# hub4.net
KiCad netlist of a schematic drawn in EAGLE
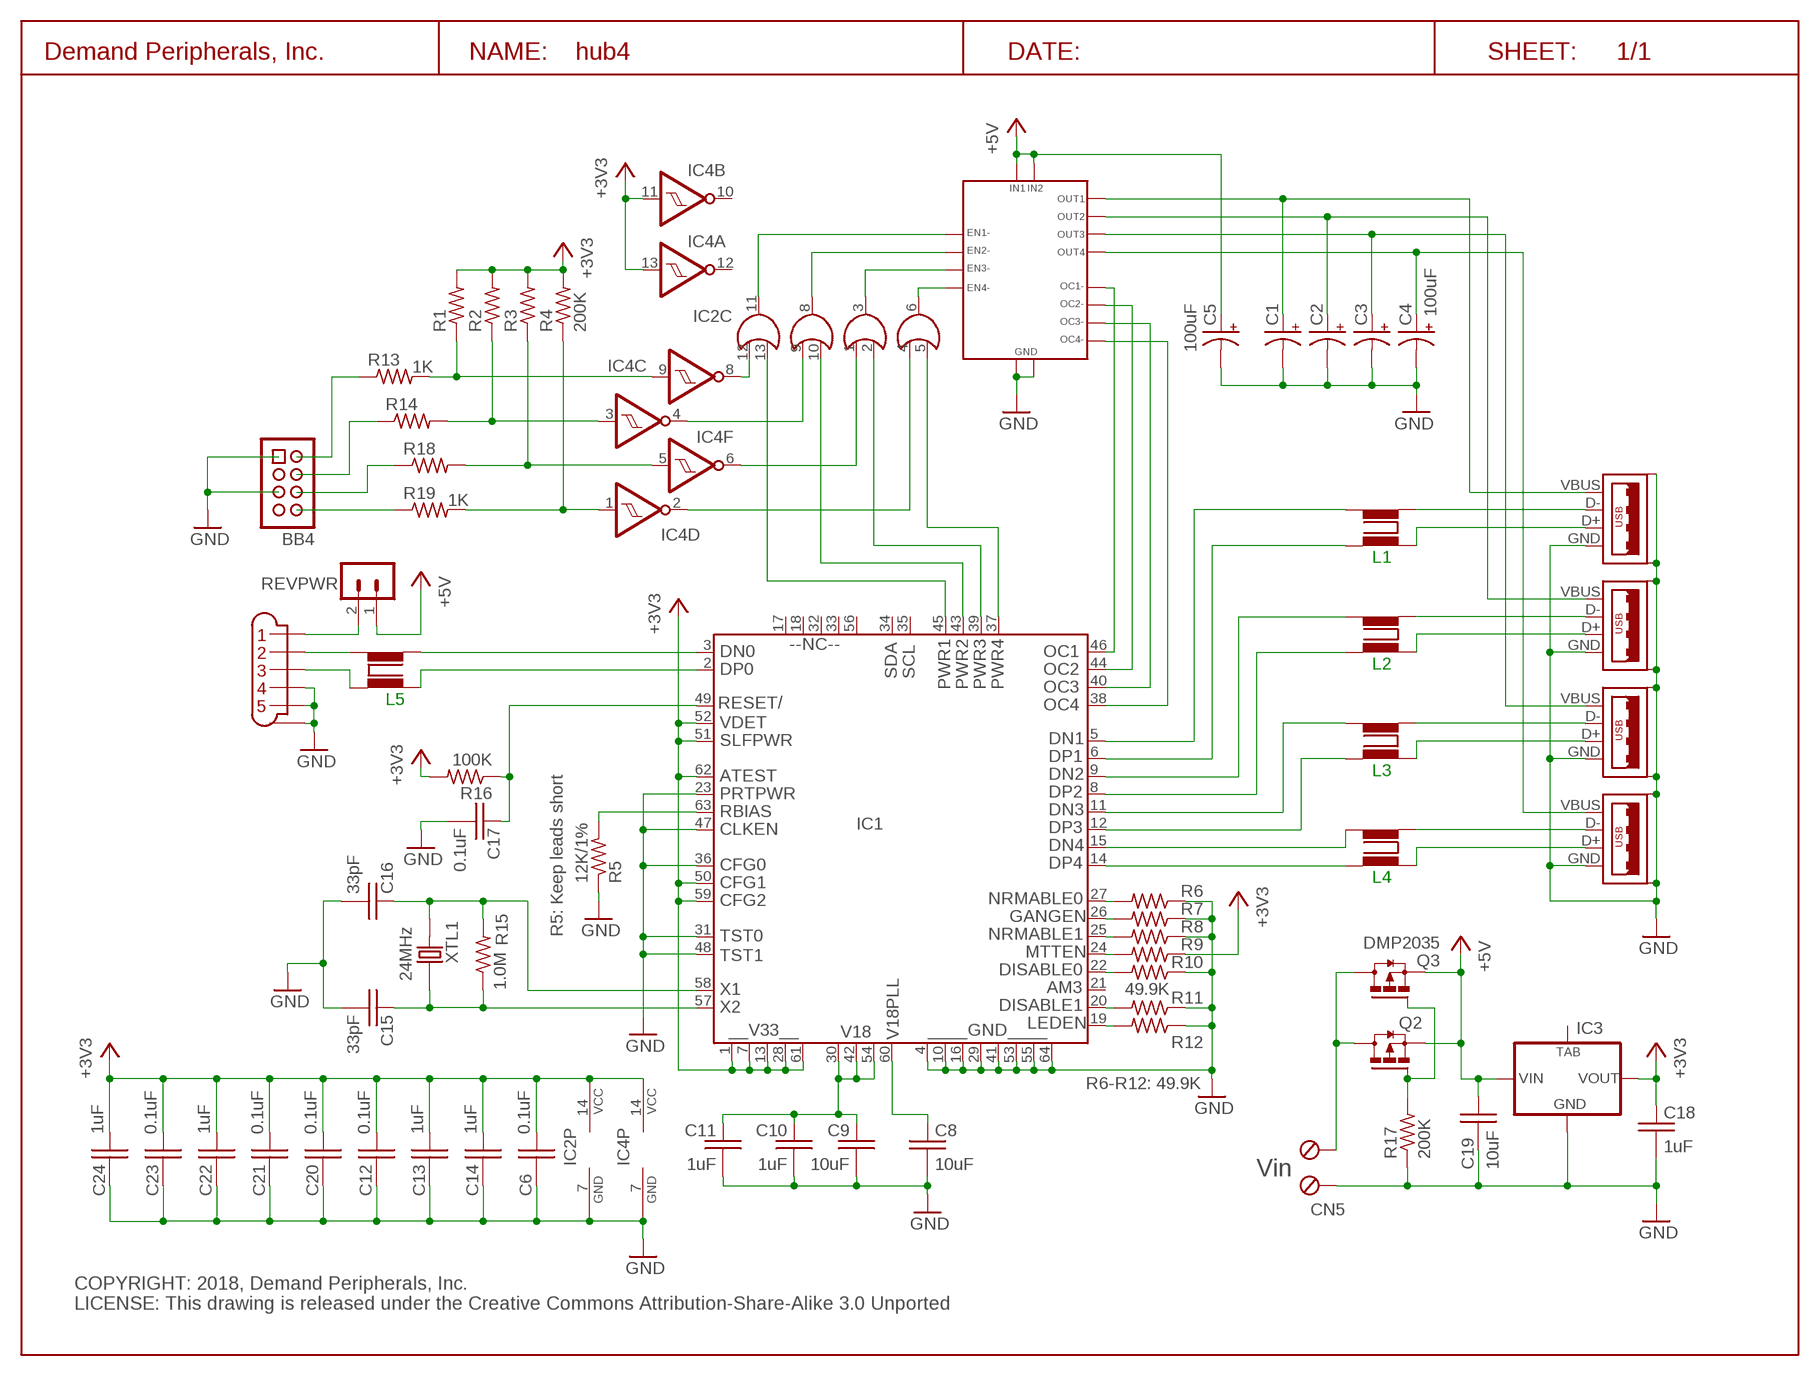
[diagram p0: schematic, sheet 1]

(export (version "E")
  (design (tool "Eeschema 10.0.6"))
  (components
    (comp (ref "BB4")
      (value "HDR-4X2-SHR")
      (footprint "eagle-import:HDR-4X2")
      (libsource (lib "eagle-import") (part "HDR-4X2-SHR"))
    )
    (comp (ref "C1")
      (value "100uF")
      (footprint "eagle-import:E3.5-8")
      (libsource (lib "eagle-import") (part "C100UF35V_E3.5-8"))
    )
    (comp (ref "C2")
      (value "100uF")
      (footprint "eagle-import:E3.5-8")
      (libsource (lib "eagle-import") (part "C100UF35V_E3.5-8"))
    )
    (comp (ref "C3")
      (value "100uF")
      (footprint "eagle-import:E3.5-8")
      (libsource (lib "eagle-import") (part "C100UF35V_E3.5-8"))
    )
    (comp (ref "C4")
      (value "100uF")
      (footprint "eagle-import:E3.5-8")
      (libsource (lib "eagle-import") (part "C100UF35V_E3.5-8"))
    )
    (comp (ref "C5")
      (value "100uF")
      (footprint "eagle-import:E3.5-8")
      (libsource (lib "eagle-import") (part "C100UF35V_E3.5-8"))
    )
    (comp (ref "C6")
      (value "0.1uF")
      (footprint "eagle-import:C0603")
      (libsource (lib "eagle-import") (part "C0.1UF_C0603"))
    )
    (comp (ref "C8")
      (value "10uF")
      (footprint "eagle-import:C0805")
      (libsource (lib "eagle-import") (part "C10UF35V_C0805"))
    )
    (comp (ref "C9")
      (value "10uF")
      (footprint "eagle-import:C0805")
      (libsource (lib "eagle-import") (part "C10UF35V_C0805"))
    )
    (comp (ref "C10")
      (value "1uF")
      (footprint "eagle-import:C0603")
      (libsource (lib "eagle-import") (part "C1.0UF_C0603"))
    )
    (comp (ref "C11")
      (value "1uF")
      (footprint "eagle-import:C0603")
      (libsource (lib "eagle-import") (part "C1.0UF_C0603"))
    )
    (comp (ref "C12")
      (value "0.1uF")
      (footprint "eagle-import:C0603")
      (libsource (lib "eagle-import") (part "C0.1UF_C0603"))
    )
    (comp (ref "C13")
      (value "1uF")
      (footprint "eagle-import:C0603")
      (libsource (lib "eagle-import") (part "C1.0UF_C0603"))
    )
    (comp (ref "C14")
      (value "1uF")
      (footprint "eagle-import:C0603")
      (libsource (lib "eagle-import") (part "C1.0UF_C0603"))
    )
    (comp (ref "C15")
      (value "33pF")
      (footprint "eagle-import:C0603")
      (libsource (lib "eagle-import") (part "C33PF_C0603"))
    )
    (comp (ref "C16")
      (value "33pF")
      (footprint "eagle-import:C0603")
      (libsource (lib "eagle-import") (part "C33PF_C0603"))
    )
    (comp (ref "C17")
      (value "0.1uF")
      (footprint "eagle-import:C0603")
      (libsource (lib "eagle-import") (part "C0.1UF_C0603"))
    )
    (comp (ref "C18")
      (value "1uF")
      (footprint "eagle-import:C0603")
      (libsource (lib "eagle-import") (part "C1.0UF_C0603"))
    )
    (comp (ref "C19")
      (value "10uF")
      (footprint "eagle-import:C0805")
      (libsource (lib "eagle-import") (part "C10UF35V_C0805"))
    )
    (comp (ref "C20")
      (value "0.1uF")
      (footprint "eagle-import:C0603")
      (libsource (lib "eagle-import") (part "C0.1UF_C0603"))
    )
    (comp (ref "C21")
      (value "0.1uF")
      (footprint "eagle-import:C0603")
      (libsource (lib "eagle-import") (part "C0.1UF_C0603"))
    )
    (comp (ref "C22")
      (value "1uF")
      (footprint "eagle-import:C0603")
      (libsource (lib "eagle-import") (part "C1.0UF_C0603"))
    )
    (comp (ref "C23")
      (value "0.1uF")
      (footprint "eagle-import:C0603")
      (libsource (lib "eagle-import") (part "C0.1UF_C0603"))
    )
    (comp (ref "C24")
      (value "1uF")
      (footprint "eagle-import:C0603")
      (libsource (lib "eagle-import") (part "C1.0UF_C0603"))
    )
    (comp (ref "CN1")
      (value "USB_SINGLETHRU-HOLE")
      (footprint "eagle-import:USB-A_1H")
      (libsource (lib "eagle-import") (part "USB_SINGLETHRU-HOLE"))
    )
    (comp (ref "CN2")
      (value "USB_SINGLETHRU-HOLE")
      (footprint "eagle-import:USB-A_1H")
      (libsource (lib "eagle-import") (part "USB_SINGLETHRU-HOLE"))
    )
    (comp (ref "CN3")
      (value "USB_SINGLETHRU-HOLE")
      (footprint "eagle-import:USB-A_1H")
      (libsource (lib "eagle-import") (part "USB_SINGLETHRU-HOLE"))
    )
    (comp (ref "CN4")
      (value "USB_SINGLETHRU-HOLE")
      (footprint "eagle-import:USB-A_1H")
      (libsource (lib "eagle-import") (part "USB_SINGLETHRU-HOLE"))
    )
    (comp (ref "CN5")
      (value "TBLK-5.08-X2")
      (footprint "eagle-import:TBLK-5.08-X2")
      (libsource (lib "eagle-import") (part "TBLK-5.08-X2"))
    )
    (comp (ref "IC1")
      (value "USB2504")
      (footprint "eagle-import:TQFP64-10X10")
      (libsource (lib "eagle-import") (part "USB2504"))
    )
    (comp (ref "IC2")
      (value "7432")
      (footprint "eagle-import:SO14")
      (libsource (lib "eagle-import") (part "7432"))
    )
    (comp (ref "IC3")
      (value "LM1117A")
      (footprint "eagle-import:SOT223")
      (libsource (lib "eagle-import") (part "LM1117A"))
    )
    (comp (ref "IC4")
      (value "7414")
      (footprint "eagle-import:SO14")
      (libsource (lib "eagle-import") (part "7414"))
    )
    (comp (ref "IC5")
      (value "TPS2044")
      (footprint "eagle-import:SO16")
      (libsource (lib "eagle-import") (part "TPS2044"))
    )
    (comp (ref "L1")
      (value "ACM2012")
      (footprint "eagle-import:ACM2012")
      (libsource (lib "eagle-import") (part "ACM2012"))
    )
    (comp (ref "L2")
      (value "ACM2012")
      (footprint "eagle-import:ACM2012")
      (libsource (lib "eagle-import") (part "ACM2012"))
    )
    (comp (ref "L3")
      (value "ACM2012")
      (footprint "eagle-import:ACM2012")
      (libsource (lib "eagle-import") (part "ACM2012"))
    )
    (comp (ref "L4")
      (value "ACM2012")
      (footprint "eagle-import:ACM2012")
      (libsource (lib "eagle-import") (part "ACM2012"))
    )
    (comp (ref "L5")
      (value "ACM2012")
      (footprint "eagle-import:ACM2012")
      (libsource (lib "eagle-import") (part "ACM2012"))
    )
    (comp (ref "Q2")
      (value "DMP2035")
      (footprint "eagle-import:SOT23")
      (libsource (lib "eagle-import") (part "DMP2035"))
    )
    (comp (ref "Q3")
      (value "DMP2035")
      (footprint "eagle-import:SOT23")
      (libsource (lib "eagle-import") (part "DMP2035"))
    )
    (comp (ref "R1")
      (value "200K")
      (footprint "eagle-import:R0603")
      (libsource (lib "eagle-import") (part "R200K_R0603"))
    )
    (comp (ref "R2")
      (value "200K")
      (footprint "eagle-import:R0603")
      (libsource (lib "eagle-import") (part "R200K_R0603"))
    )
    (comp (ref "R3")
      (value "200K")
      (footprint "eagle-import:R0603")
      (libsource (lib "eagle-import") (part "R200K_R0603"))
    )
    (comp (ref "R4")
      (value "200K")
      (footprint "eagle-import:R0603")
      (libsource (lib "eagle-import") (part "R200K_R0603"))
    )
    (comp (ref "R5")
      (value "12K/1%")
      (footprint "eagle-import:R0603")
      (libsource (lib "eagle-import") (part "R12K_R0603"))
    )
    (comp (ref "R6")
      (value "49.9K")
      (footprint "eagle-import:R0603")
      (libsource (lib "eagle-import") (part "R49.9K_R0603"))
    )
    (comp (ref "R7")
      (value "49.9K")
      (footprint "eagle-import:R0603")
      (libsource (lib "eagle-import") (part "R49.9K_R0603"))
    )
    (comp (ref "R8")
      (value "49.9K")
      (footprint "eagle-import:R0603")
      (libsource (lib "eagle-import") (part "R49.9K_R0603"))
    )
    (comp (ref "R9")
      (value "49.9K")
      (footprint "eagle-import:R0603")
      (libsource (lib "eagle-import") (part "R49.9K_R0603"))
    )
    (comp (ref "R10")
      (value "49.9K")
      (footprint "eagle-import:R0603")
      (libsource (lib "eagle-import") (part "R49.9K_R0603"))
    )
    (comp (ref "R11")
      (value "49.9K")
      (footprint "eagle-import:R0603")
      (libsource (lib "eagle-import") (part "R49.9K_R0603"))
    )
    (comp (ref "R12")
      (value "49.9K")
      (footprint "eagle-import:R0603")
      (libsource (lib "eagle-import") (part "R49.9K_R0603"))
    )
    (comp (ref "R13")
      (value "1K")
      (footprint "eagle-import:R0603")
      (libsource (lib "eagle-import") (part "R1K_R0603"))
    )
    (comp (ref "R14")
      (value "1K")
      (footprint "eagle-import:R0603")
      (libsource (lib "eagle-import") (part "R1K_R0603"))
    )
    (comp (ref "R15")
      (value "1.0M")
      (footprint "eagle-import:R0603")
      (libsource (lib "eagle-import") (part "R1M_R0603"))
    )
    (comp (ref "R16")
      (value "100K")
      (footprint "eagle-import:R0603")
      (libsource (lib "eagle-import") (part "R100K_R0603"))
    )
    (comp (ref "R17")
      (value "200K")
      (footprint "eagle-import:R0603")
      (libsource (lib "eagle-import") (part "R200K_R0603"))
    )
    (comp (ref "R18")
      (value "1K")
      (footprint "eagle-import:R0603")
      (libsource (lib "eagle-import") (part "R1K_R0603"))
    )
    (comp (ref "R19")
      (value "1K")
      (footprint "eagle-import:R0603")
      (libsource (lib "eagle-import") (part "R1K_R0603"))
    )
    (comp (ref "REVPWR")
      (value "HDR-2X1-LCK")
      (footprint "eagle-import:HDR-2X1")
      (libsource (lib "eagle-import") (part "HDR-2X1-LCK"))
    )
    (comp (ref "U$5")
      (value "MINI-B")
      (footprint "eagle-import:MINI-B-MOLEX")
      (libsource (lib "eagle-import") (part "MINI-B"))
    )
    (comp (ref "U$6")
      (value "DP_FRAME_L")
      (footprint "eagle-import:LETTER_L")
      (libsource (lib "eagle-import") (part "DP_FRAME_L"))
    )
    (comp (ref "XTL1")
      (value "24MHz")
      (footprint "eagle-import:HC49S")
      (libsource (lib "eagle-import") (part "HC49S-24MHZ"))
    )
  )
  (nets
    (net (code "1") (name "+3V3") (class "Default")
      (node (ref "C12") (pin "1") (pinfunction "1_1") (pintype "passive"))
      (node (ref "C13") (pin "1") (pinfunction "1_1") (pintype "passive"))
      (node (ref "C14") (pin "1") (pinfunction "1_1") (pintype "passive"))
      (node (ref "C18") (pin "1") (pinfunction "1_1") (pintype "passive"))
      (node (ref "C20") (pin "1") (pinfunction "1_1") (pintype "passive"))
      (node (ref "C21") (pin "1") (pinfunction "1_1") (pintype "passive"))
      (node (ref "C22") (pin "1") (pinfunction "1_1") (pintype "passive"))
      (node (ref "C23") (pin "1") (pinfunction "1_1") (pintype "passive"))
      (node (ref "C24") (pin "1") (pinfunction "1_1") (pintype "passive"))
      (node (ref "C6") (pin "1") (pinfunction "1_1") (pintype "passive"))
      (node (ref "IC1") (pin "1") (pinfunction "V33-0_1") (pintype "power_in"))
      (node (ref "IC1") (pin "13") (pinfunction "V33-2_13") (pintype "power_in"))
      (node (ref "IC1") (pin "28") (pinfunction "V33-3_28") (pintype "power_in"))
      (node (ref "IC1") (pin "50") (pinfunction "CFG1_50") (pintype "passive"))
      (node (ref "IC1") (pin "51") (pinfunction "SLFPWR_51") (pintype "passive"))
      (node (ref "IC1") (pin "52") (pinfunction "VDET_52") (pintype "passive"))
      (node (ref "IC1") (pin "59") (pinfunction "CFG2_59") (pintype "passive"))
      (node (ref "IC1") (pin "61") (pinfunction "V33-PLL_61") (pintype "power_in"))
      (node (ref "IC1") (pin "62") (pinfunction "ATEST_62") (pintype "passive"))
      (node (ref "IC1") (pin "7") (pinfunction "V33-1_7") (pintype "power_in"))
      (node (ref "IC2") (pin "14") (pinfunction "VCC_14") (pintype "power_in"))
      (node (ref "IC3") (pin "2") (pinfunction "OUT_2") (pintype "passive"))
      (node (ref "IC4") (pin "11") (pinfunction "I_11") (pintype "input"))
      (node (ref "IC4") (pin "13") (pinfunction "I_13") (pintype "input"))
      (node (ref "IC4") (pin "14") (pinfunction "VCC_14") (pintype "power_in"))
      (node (ref "R1") (pin "2") (pinfunction "2_2") (pintype "passive"))
      (node (ref "R16") (pin "2") (pinfunction "2_2") (pintype "passive"))
      (node (ref "R2") (pin "2") (pinfunction "2_2") (pintype "passive"))
      (node (ref "R3") (pin "2") (pinfunction "2_2") (pintype "passive"))
      (node (ref "R4") (pin "2") (pinfunction "2_2") (pintype "passive"))
      (node (ref "R9") (pin "1") (pinfunction "1_1") (pintype "passive"))
    )
    (net (code "2") (name "+5V") (class "Default")
      (node (ref "C19") (pin "1") (pinfunction "1_1") (pintype "passive"))
      (node (ref "C5") (pin "+") (pinfunction "+_+") (pintype "passive"))
      (node (ref "IC3") (pin "3") (pinfunction "IN_3") (pintype "input"))
      (node (ref "IC5") (pin "2") (pinfunction "IN1_2") (pintype "power_in"))
      (node (ref "IC5") (pin "6") (pinfunction "IN2_6") (pintype "power_in"))
      (node (ref "Q2") (pin "2") (pinfunction "S_2") (pintype "passive"))
      (node (ref "Q3") (pin "2") (pinfunction "S_2") (pintype "passive"))
      (node (ref "REVPWR") (pin "1") (pinfunction "2_1") (pintype "passive"))
    )
    (net (code "3") (name "GND") (class "Default")
      (node (ref "BB4") (pin "1") (pinfunction "1_1") (pintype "passive"))
      (node (ref "BB4") (pin "5") (pinfunction "5_5") (pintype "passive"))
      (node (ref "C1") (pin "-") (pinfunction "-_-") (pintype "passive"))
      (node (ref "C10") (pin "2") (pinfunction "2_2") (pintype "passive"))
      (node (ref "C11") (pin "2") (pinfunction "2_2") (pintype "passive"))
      (node (ref "C12") (pin "2") (pinfunction "2_2") (pintype "passive"))
      (node (ref "C13") (pin "2") (pinfunction "2_2") (pintype "passive"))
      (node (ref "C14") (pin "2") (pinfunction "2_2") (pintype "passive"))
      (node (ref "C15") (pin "2") (pinfunction "2_2") (pintype "passive"))
      (node (ref "C16") (pin "2") (pinfunction "2_2") (pintype "passive"))
      (node (ref "C17") (pin "2") (pinfunction "2_2") (pintype "passive"))
      (node (ref "C18") (pin "2") (pinfunction "2_2") (pintype "passive"))
      (node (ref "C19") (pin "2") (pinfunction "2_2") (pintype "passive"))
      (node (ref "C2") (pin "-") (pinfunction "-_-") (pintype "passive"))
      (node (ref "C20") (pin "2") (pinfunction "2_2") (pintype "passive"))
      (node (ref "C21") (pin "2") (pinfunction "2_2") (pintype "passive"))
      (node (ref "C22") (pin "2") (pinfunction "2_2") (pintype "passive"))
      (node (ref "C23") (pin "2") (pinfunction "2_2") (pintype "passive"))
      (node (ref "C24") (pin "2") (pinfunction "2_2") (pintype "passive"))
      (node (ref "C3") (pin "-") (pinfunction "-_-") (pintype "passive"))
      (node (ref "C4") (pin "-") (pinfunction "-_-") (pintype "passive"))
      (node (ref "C5") (pin "-") (pinfunction "-_-") (pintype "passive"))
      (node (ref "C6") (pin "2") (pinfunction "2_2") (pintype "passive"))
      (node (ref "C8") (pin "2") (pinfunction "2_2") (pintype "passive"))
      (node (ref "C9") (pin "2") (pinfunction "2_2") (pintype "passive"))
      (node (ref "CN1") (pin "GND") (pinfunction "4_GND") (pintype "passive"))
      (node (ref "CN1") (pin "P$5") (pinfunction "5_P$5") (pintype "passive"))
      (node (ref "CN1") (pin "P$6") (pinfunction "6_P$6") (pintype "passive"))
      (node (ref "CN2") (pin "GND") (pinfunction "4_GND") (pintype "passive"))
      (node (ref "CN2") (pin "P$5") (pinfunction "5_P$5") (pintype "passive"))
      (node (ref "CN2") (pin "P$6") (pinfunction "6_P$6") (pintype "passive"))
      (node (ref "CN3") (pin "GND") (pinfunction "4_GND") (pintype "passive"))
      (node (ref "CN3") (pin "P$5") (pinfunction "5_P$5") (pintype "passive"))
      (node (ref "CN3") (pin "P$6") (pinfunction "6_P$6") (pintype "passive"))
      (node (ref "CN4") (pin "GND") (pinfunction "4_GND") (pintype "passive"))
      (node (ref "CN4") (pin "P$5") (pinfunction "5_P$5") (pintype "passive"))
      (node (ref "CN4") (pin "P$6") (pinfunction "6_P$6") (pintype "passive"))
      (node (ref "CN5") (pin "1") (pinfunction "KL_1") (pintype "passive"))
      (node (ref "IC1") (pin "10") (pinfunction "VSS1_10") (pintype "power_in"))
      (node (ref "IC1") (pin "16") (pinfunction "VSS2_16") (pintype "power_in"))
      (node (ref "IC1") (pin "23") (pinfunction "PTRPWR_23") (pintype "passive"))
      (node (ref "IC1") (pin "29") (pinfunction "VSS3_29") (pintype "power_in"))
      (node (ref "IC1") (pin "31") (pinfunction "TST0_31") (pintype "passive"))
      (node (ref "IC1") (pin "36") (pinfunction "CFG0_36") (pintype "passive"))
      (node (ref "IC1") (pin "4") (pinfunction "VSS0_4") (pintype "power_in"))
      (node (ref "IC1") (pin "41") (pinfunction "VSS4_41") (pintype "power_in"))
      (node (ref "IC1") (pin "47") (pinfunction "CLKEN_47") (pintype "passive"))
      (node (ref "IC1") (pin "48") (pinfunction "TST1_48") (pintype "passive"))
      (node (ref "IC1") (pin "53") (pinfunction "VSS5_53") (pintype "power_in"))
      (node (ref "IC1") (pin "55") (pinfunction "VSS6_55") (pintype "power_in"))
      (node (ref "IC1") (pin "64") (pinfunction "VSS7_64") (pintype "power_in"))
      (node (ref "IC2") (pin "7") (pinfunction "GND_7") (pintype "power_in"))
      (node (ref "IC3") (pin "1") (pinfunction "GND_1") (pintype "input"))
      (node (ref "IC4") (pin "7") (pinfunction "GND_7") (pintype "power_in"))
      (node (ref "IC5") (pin "1") (pinfunction "GND1_1") (pintype "power_in"))
      (node (ref "IC5") (pin "5") (pinfunction "GND2_5") (pintype "power_in"))
      (node (ref "R10") (pin "1") (pinfunction "1_1") (pintype "passive"))
      (node (ref "R11") (pin "1") (pinfunction "1_1") (pintype "passive"))
      (node (ref "R12") (pin "1") (pinfunction "1_1") (pintype "passive"))
      (node (ref "R17") (pin "1") (pinfunction "1_1") (pintype "passive"))
      (node (ref "R5") (pin "1") (pinfunction "1_1") (pintype "passive"))
      (node (ref "R6") (pin "1") (pinfunction "1_1") (pintype "passive"))
      (node (ref "R7") (pin "1") (pinfunction "1_1") (pintype "passive"))
      (node (ref "R8") (pin "1") (pinfunction "1_1") (pintype "passive"))
      (node (ref "U$5") (pin "GND") (pinfunction "GND_GND") (pintype "power_in"))
      (node (ref "U$5") (pin "P$4") (pinfunction "P$4_P$4") (pintype "bidirectional"))
      (node (ref "U$5") (pin "P$5") (pinfunction "P$5_P$5") (pintype "bidirectional"))
    )
    (net (code "4") (name "Net-(BB4-Pad2)") (class "Default")
      (node (ref "BB4") (pin "2") (pinfunction "2_2") (pintype "passive"))
      (node (ref "R13") (pin "1") (pinfunction "1_1") (pintype "passive"))
    )
    (net (code "5") (name "Net-(BB4-Pad4)") (class "Default")
      (node (ref "BB4") (pin "4") (pinfunction "4_4") (pintype "passive"))
      (node (ref "R14") (pin "1") (pinfunction "1_1") (pintype "passive"))
    )
    (net (code "6") (name "Net-(BB4-Pad6)") (class "Default")
      (node (ref "BB4") (pin "6") (pinfunction "6_6") (pintype "passive"))
      (node (ref "R18") (pin "1") (pinfunction "1_1") (pintype "passive"))
    )
    (net (code "7") (name "Net-(BB4-Pad8)") (class "Default")
      (node (ref "BB4") (pin "8") (pinfunction "8_8") (pintype "passive"))
      (node (ref "R19") (pin "1") (pinfunction "1_1") (pintype "passive"))
    )
    (net (code "8") (name "Net-(CN1-1)") (class "Default")
      (node (ref "C1") (pin "+") (pinfunction "+_+") (pintype "passive"))
      (node (ref "CN1") (pin "VBUS") (pinfunction "1_VBUS") (pintype "passive"))
      (node (ref "IC5") (pin "15") (pinfunction "OUT1_15") (pintype "passive"))
    )
    (net (code "9") (name "Net-(CN1-2)") (class "Default")
      (node (ref "CN1") (pin "D-") (pinfunction "2_D-") (pintype "passive"))
      (node (ref "L1") (pin "P$3") (pinfunction "3_P$3") (pintype "passive"))
    )
    (net (code "10") (name "Net-(CN1-3)") (class "Default")
      (node (ref "CN1") (pin "D+") (pinfunction "3_D+") (pintype "passive"))
      (node (ref "L1") (pin "P$1") (pinfunction "1_P$1") (pintype "passive"))
    )
    (net (code "11") (name "Net-(CN2-1)") (class "Default")
      (node (ref "C2") (pin "+") (pinfunction "+_+") (pintype "passive"))
      (node (ref "CN2") (pin "VBUS") (pinfunction "1_VBUS") (pintype "passive"))
      (node (ref "IC5") (pin "14") (pinfunction "OUT2_14") (pintype "passive"))
    )
    (net (code "12") (name "Net-(CN2-2)") (class "Default")
      (node (ref "CN2") (pin "D-") (pinfunction "2_D-") (pintype "passive"))
      (node (ref "L2") (pin "P$1") (pinfunction "1_P$1") (pintype "passive"))
    )
    (net (code "13") (name "Net-(CN2-3)") (class "Default")
      (node (ref "CN2") (pin "D+") (pinfunction "3_D+") (pintype "passive"))
      (node (ref "L2") (pin "P$3") (pinfunction "3_P$3") (pintype "passive"))
    )
    (net (code "14") (name "Net-(CN3-1)") (class "Default")
      (node (ref "C3") (pin "+") (pinfunction "+_+") (pintype "passive"))
      (node (ref "CN3") (pin "VBUS") (pinfunction "1_VBUS") (pintype "passive"))
      (node (ref "IC5") (pin "11") (pinfunction "OUT3_11") (pintype "passive"))
    )
    (net (code "15") (name "Net-(CN3-2)") (class "Default")
      (node (ref "CN3") (pin "D-") (pinfunction "2_D-") (pintype "passive"))
      (node (ref "L3") (pin "P$3") (pinfunction "3_P$3") (pintype "passive"))
    )
    (net (code "16") (name "Net-(CN3-3)") (class "Default")
      (node (ref "CN3") (pin "D+") (pinfunction "3_D+") (pintype "passive"))
      (node (ref "L3") (pin "P$1") (pinfunction "1_P$1") (pintype "passive"))
    )
    (net (code "17") (name "Net-(CN4-1)") (class "Default")
      (node (ref "C4") (pin "+") (pinfunction "+_+") (pintype "passive"))
      (node (ref "CN4") (pin "VBUS") (pinfunction "1_VBUS") (pintype "passive"))
      (node (ref "IC5") (pin "10") (pinfunction "OUT4_10") (pintype "passive"))
    )
    (net (code "18") (name "Net-(CN4-2)") (class "Default")
      (node (ref "CN4") (pin "D-") (pinfunction "2_D-") (pintype "passive"))
      (node (ref "L4") (pin "P$1") (pinfunction "1_P$1") (pintype "passive"))
    )
    (net (code "19") (name "Net-(CN4-3)") (class "Default")
      (node (ref "CN4") (pin "D+") (pinfunction "3_D+") (pintype "passive"))
      (node (ref "L4") (pin "P$3") (pinfunction "3_P$3") (pintype "passive"))
    )
    (net (code "20") (name "Net-(CN5-KL1)") (class "Default")
      (node (ref "CN5") (pin "2") (pinfunction "KL1_2") (pintype "passive"))
      (node (ref "Q2") (pin "3") (pinfunction "D_3") (pintype "passive"))
      (node (ref "Q3") (pin "3") (pinfunction "D_3") (pintype "passive"))
    )
    (net (code "21") (name "Net-(IC1-AM1)") (class "Default")
      (node (ref "IC1") (pin "26") (pinfunction "AM1_26") (pintype "output"))
      (node (ref "R7") (pin "2") (pinfunction "2_2") (pintype "passive"))
    )
    (net (code "22") (name "Net-(IC1-AM2)") (class "Default")
      (node (ref "IC1") (pin "24") (pinfunction "AM2_24") (pintype "output"))
      (node (ref "R9") (pin "2") (pinfunction "2_2") (pintype "passive"))
    )
    (net (code "23") (name "Net-(IC1-AM4)") (class "Default")
      (node (ref "IC1") (pin "19") (pinfunction "AM4_19") (pintype "output"))
      (node (ref "R12") (pin "2") (pinfunction "2_2") (pintype "passive"))
    )
    (net (code "24") (name "Net-(IC1-DN0)") (class "Default")
      (node (ref "IC1") (pin "3") (pinfunction "DN0_3") (pintype "passive"))
      (node (ref "L5") (pin "P$2") (pinfunction "2_P$2") (pintype "passive"))
    )
    (net (code "25") (name "Net-(IC1-DN1)") (class "Default")
      (node (ref "IC1") (pin "5") (pinfunction "DN1_5") (pintype "passive"))
      (node (ref "L1") (pin "P$4") (pinfunction "4_P$4") (pintype "passive"))
    )
    (net (code "26") (name "Net-(IC1-DN2)") (class "Default")
      (node (ref "IC1") (pin "9") (pinfunction "DN2_9") (pintype "passive"))
      (node (ref "L2") (pin "P$2") (pinfunction "2_P$2") (pintype "passive"))
    )
    (net (code "27") (name "Net-(IC1-DN3)") (class "Default")
      (node (ref "IC1") (pin "11") (pinfunction "DN3_11") (pintype "passive"))
      (node (ref "L3") (pin "P$4") (pinfunction "4_P$4") (pintype "passive"))
    )
    (net (code "28") (name "Net-(IC1-DN4)") (class "Default")
      (node (ref "IC1") (pin "15") (pinfunction "DN4_15") (pintype "passive"))
      (node (ref "L4") (pin "P$2") (pinfunction "2_P$2") (pintype "passive"))
    )
    (net (code "29") (name "Net-(IC1-DP0)") (class "Default")
      (node (ref "IC1") (pin "2") (pinfunction "DP0_2") (pintype "passive"))
      (node (ref "L5") (pin "P$4") (pinfunction "4_P$4") (pintype "passive"))
    )
    (net (code "30") (name "Net-(IC1-DP1)") (class "Default")
      (node (ref "IC1") (pin "6") (pinfunction "DP1_6") (pintype "passive"))
      (node (ref "L1") (pin "P$2") (pinfunction "2_P$2") (pintype "passive"))
    )
    (net (code "31") (name "Net-(IC1-DP2)") (class "Default")
      (node (ref "IC1") (pin "8") (pinfunction "DP2_8") (pintype "passive"))
      (node (ref "L2") (pin "P$4") (pinfunction "4_P$4") (pintype "passive"))
    )
    (net (code "32") (name "Net-(IC1-DP3)") (class "Default")
      (node (ref "IC1") (pin "12") (pinfunction "DP3_12") (pintype "passive"))
      (node (ref "L3") (pin "P$2") (pinfunction "2_P$2") (pintype "passive"))
    )
    (net (code "33") (name "Net-(IC1-DP4)") (class "Default")
      (node (ref "IC1") (pin "14") (pinfunction "DP4_14") (pintype "passive"))
      (node (ref "L4") (pin "P$4") (pinfunction "4_P$4") (pintype "passive"))
    )
    (net (code "34") (name "Net-(IC1-GR1)") (class "Default")
      (node (ref "IC1") (pin "27") (pinfunction "GR1_27") (pintype "output"))
      (node (ref "R6") (pin "2") (pinfunction "2_2") (pintype "passive"))
    )
    (net (code "35") (name "Net-(IC1-GR2)") (class "Default")
      (node (ref "IC1") (pin "25") (pinfunction "GR2_25") (pintype "output"))
      (node (ref "R8") (pin "2") (pinfunction "2_2") (pintype "passive"))
    )
    (net (code "36") (name "Net-(IC1-GR3)") (class "Default")
      (node (ref "IC1") (pin "22") (pinfunction "GR3_22") (pintype "output"))
      (node (ref "R10") (pin "2") (pinfunction "2_2") (pintype "passive"))
    )
    (net (code "37") (name "Net-(IC1-GR4)") (class "Default")
      (node (ref "IC1") (pin "20") (pinfunction "GR4_20") (pintype "output"))
      (node (ref "R11") (pin "2") (pinfunction "2_2") (pintype "passive"))
    )
    (net (code "38") (name "Net-(IC1-OC1)") (class "Default")
      (node (ref "IC1") (pin "46") (pinfunction "OC1_46") (pintype "input"))
      (node (ref "IC5") (pin "16") (pinfunction "OC1-_16") (pintype "output"))
    )
    (net (code "39") (name "Net-(IC1-OC2)") (class "Default")
      (node (ref "IC1") (pin "44") (pinfunction "OC2_44") (pintype "input"))
      (node (ref "IC5") (pin "13") (pinfunction "OC2-_13") (pintype "output"))
    )
    (net (code "40") (name "Net-(IC1-OC3)") (class "Default")
      (node (ref "IC1") (pin "40") (pinfunction "OC3_40") (pintype "input"))
      (node (ref "IC5") (pin "12") (pinfunction "OC3-_12") (pintype "output"))
    )
    (net (code "41") (name "Net-(IC1-OC4)") (class "Default")
      (node (ref "IC1") (pin "38") (pinfunction "OC4_38") (pintype "input"))
      (node (ref "IC5") (pin "9") (pinfunction "OC4-_9") (pintype "output"))
    )
    (net (code "42") (name "Net-(IC1-PWR1)") (class "Default")
      (node (ref "IC1") (pin "45") (pinfunction "PWR1_45") (pintype "output"))
      (node (ref "IC2") (pin "13") (pinfunction "I1_13") (pintype "input"))
    )
    (net (code "43") (name "Net-(IC1-PWR2)") (class "Default")
      (node (ref "IC1") (pin "43") (pinfunction "PWR2_43") (pintype "output"))
      (node (ref "IC2") (pin "10") (pinfunction "I1_10") (pintype "input"))
    )
    (net (code "44") (name "Net-(IC1-PWR3)") (class "Default")
      (node (ref "IC1") (pin "39") (pinfunction "PWR3_39") (pintype "output"))
      (node (ref "IC2") (pin "2") (pinfunction "I1_2") (pintype "input"))
    )
    (net (code "45") (name "Net-(IC1-PWR4)") (class "Default")
      (node (ref "IC1") (pin "37") (pinfunction "PWR4_37") (pintype "output"))
      (node (ref "IC2") (pin "5") (pinfunction "I1_5") (pintype "input"))
    )
    (net (code "46") (name "Net-(IC1-RBIAS)") (class "Default")
      (node (ref "IC1") (pin "63") (pinfunction "RBIAS_63") (pintype "passive"))
      (node (ref "R5") (pin "2") (pinfunction "2_2") (pintype "passive"))
    )
    (net (code "47") (name "Net-(IC1-RESET)") (class "Default")
      (node (ref "C17") (pin "1") (pinfunction "1_1") (pintype "passive"))
      (node (ref "IC1") (pin "49") (pinfunction "RESET_49") (pintype "passive"))
      (node (ref "R16") (pin "1") (pinfunction "1_1") (pintype "passive"))
    )
    (net (code "48") (name "Net-(IC1-V18-0)") (class "Default")
      (node (ref "C10") (pin "1") (pinfunction "1_1") (pintype "passive"))
      (node (ref "C11") (pin "1") (pinfunction "1_1") (pintype "passive"))
      (node (ref "C9") (pin "1") (pinfunction "1_1") (pintype "passive"))
      (node (ref "IC1") (pin "30") (pinfunction "V18-0_30") (pintype "power_in"))
      (node (ref "IC1") (pin "42") (pinfunction "V18-1_42") (pintype "power_in"))
      (node (ref "IC1") (pin "54") (pinfunction "V18-3_54") (pintype "power_in"))
    )
    (net (code "49") (name "Net-(IC1-V18PLL)") (class "Default")
      (node (ref "C8") (pin "1") (pinfunction "1_1") (pintype "passive"))
      (node (ref "IC1") (pin "60") (pinfunction "V18PLL_60") (pintype "power_in"))
    )
    (net (code "50") (name "Net-(IC1-X1)") (class "Default")
      (node (ref "C16") (pin "1") (pinfunction "1_1") (pintype "passive"))
      (node (ref "IC1") (pin "58") (pinfunction "X1_58") (pintype "passive"))
      (node (ref "R15") (pin "2") (pinfunction "2_2") (pintype "passive"))
      (node (ref "XTL1") (pin "P$2") (pinfunction "2_P$2") (pintype "passive"))
    )
    (net (code "51") (name "Net-(IC1-X2)") (class "Default")
      (node (ref "C15") (pin "1") (pinfunction "1_1") (pintype "passive"))
      (node (ref "IC1") (pin "57") (pinfunction "X2_57") (pintype "passive"))
      (node (ref "R15") (pin "1") (pinfunction "1_1") (pintype "passive"))
      (node (ref "XTL1") (pin "P$1") (pinfunction "1_P$1") (pintype "passive"))
    )
    (net (code "52") (name "Net-(IC2A-I0)") (class "Default")
      (node (ref "IC2") (pin "1") (pinfunction "I0_1") (pintype "input"))
      (node (ref "IC4") (pin "6") (pinfunction "O_6") (pintype "output"))
    )
    (net (code "53") (name "Net-(IC2A-O)") (class "Default")
      (node (ref "IC2") (pin "3") (pinfunction "O_3") (pintype "output"))
      (node (ref "IC5") (pin "7") (pinfunction "EN3-_7") (pintype "input"))
    )
    (net (code "54") (name "Net-(IC2B-I0)") (class "Default")
      (node (ref "IC2") (pin "4") (pinfunction "I0_4") (pintype "input"))
      (node (ref "IC4") (pin "2") (pinfunction "O_2") (pintype "output"))
    )
    (net (code "55") (name "Net-(IC2B-O)") (class "Default")
      (node (ref "IC2") (pin "6") (pinfunction "O_6") (pintype "output"))
      (node (ref "IC5") (pin "8") (pinfunction "EN4-_8") (pintype "input"))
    )
    (net (code "56") (name "Net-(IC2C-I0)") (class "Default")
      (node (ref "IC2") (pin "9") (pinfunction "I0_9") (pintype "input"))
      (node (ref "IC4") (pin "4") (pinfunction "O_4") (pintype "output"))
    )
    (net (code "57") (name "Net-(IC2C-O)") (class "Default")
      (node (ref "IC2") (pin "8") (pinfunction "O_8") (pintype "output"))
      (node (ref "IC5") (pin "4") (pinfunction "EN2-_4") (pintype "input"))
    )
    (net (code "58") (name "Net-(IC2D-I0)") (class "Default")
      (node (ref "IC2") (pin "12") (pinfunction "I0_12") (pintype "input"))
      (node (ref "IC4") (pin "8") (pinfunction "O_8") (pintype "output"))
    )
    (net (code "59") (name "Net-(IC2D-O)") (class "Default")
      (node (ref "IC2") (pin "11") (pinfunction "O_11") (pintype "output"))
      (node (ref "IC5") (pin "3") (pinfunction "EN1-_3") (pintype "input"))
    )
    (net (code "60") (name "Net-(IC4C-I)") (class "Default")
      (node (ref "IC4") (pin "9") (pinfunction "I_9") (pintype "input"))
      (node (ref "R1") (pin "1") (pinfunction "1_1") (pintype "passive"))
      (node (ref "R13") (pin "2") (pinfunction "2_2") (pintype "passive"))
    )
    (net (code "61") (name "Net-(IC4D-I)") (class "Default")
      (node (ref "IC4") (pin "1") (pinfunction "I_1") (pintype "input"))
      (node (ref "R19") (pin "2") (pinfunction "2_2") (pintype "passive"))
      (node (ref "R4") (pin "1") (pinfunction "1_1") (pintype "passive"))
    )
    (net (code "62") (name "Net-(IC4E-I)") (class "Default")
      (node (ref "IC4") (pin "3") (pinfunction "I_3") (pintype "input"))
      (node (ref "R14") (pin "2") (pinfunction "2_2") (pintype "passive"))
      (node (ref "R2") (pin "1") (pinfunction "1_1") (pintype "passive"))
    )
    (net (code "63") (name "Net-(IC4F-I)") (class "Default")
      (node (ref "IC4") (pin "5") (pinfunction "I_5") (pintype "input"))
      (node (ref "R18") (pin "2") (pinfunction "2_2") (pintype "passive"))
      (node (ref "R3") (pin "1") (pinfunction "1_1") (pintype "passive"))
    )
    (net (code "64") (name "Net-(L5-1)") (class "Default")
      (node (ref "L5") (pin "P$1") (pinfunction "1_P$1") (pintype "passive"))
      (node (ref "U$5") (pin "P$2") (pinfunction "P$2_P$2") (pintype "bidirectional"))
    )
    (net (code "65") (name "Net-(L5-3)") (class "Default")
      (node (ref "L5") (pin "P$3") (pinfunction "3_P$3") (pintype "passive"))
      (node (ref "U$5") (pin "P$3") (pinfunction "P$3_P$3") (pintype "bidirectional"))
    )
    (net (code "66") (name "Net-(Q2-G)") (class "Default")
      (node (ref "Q2") (pin "1") (pinfunction "G_1") (pintype "passive"))
      (node (ref "Q3") (pin "1") (pinfunction "G_1") (pintype "passive"))
      (node (ref "R17") (pin "2") (pinfunction "2_2") (pintype "passive"))
    )
    (net (code "67") (name "Net-(REVPWR-1)") (class "Default")
      (node (ref "REVPWR") (pin "2") (pinfunction "1_2") (pintype "passive"))
      (node (ref "U$5") (pin "P$1") (pinfunction "P$1_P$1") (pintype "bidirectional"))
    )
    (net (code "68") (name "unconnected-(BB4-Pad3)") (class "Default")
      (node (ref "BB4") (pin "3") (pinfunction "3_3") (pintype "passive"))
    )
    (net (code "69") (name "unconnected-(BB4-Pad7)") (class "Default")
      (node (ref "BB4") (pin "7") (pinfunction "7_7") (pintype "passive"))
    )
    (net (code "70") (name "unconnected-(IC1-AM3-Pad21)") (class "Default")
      (node (ref "IC1") (pin "21") (pinfunction "AM3_21") (pintype "output"))
    )
    (net (code "71") (name "unconnected-(IC1-NC0-Pad17)") (class "Default")
      (node (ref "IC1") (pin "17") (pinfunction "NC0_17") (pintype "no_connect"))
    )
    (net (code "72") (name "unconnected-(IC1-NC1-Pad18)") (class "Default")
      (node (ref "IC1") (pin "18") (pinfunction "NC1_18") (pintype "no_connect"))
    )
    (net (code "73") (name "unconnected-(IC1-NC2-Pad32)") (class "Default")
      (node (ref "IC1") (pin "32") (pinfunction "NC2_32") (pintype "no_connect"))
    )
    (net (code "74") (name "unconnected-(IC1-NC3-Pad33)") (class "Default")
      (node (ref "IC1") (pin "33") (pinfunction "NC3_33") (pintype "no_connect"))
    )
    (net (code "75") (name "unconnected-(IC1-NC4-Pad56)") (class "Default")
      (node (ref "IC1") (pin "56") (pinfunction "NC4_56") (pintype "no_connect"))
    )
    (net (code "76") (name "unconnected-(IC1-SCL-Pad35)") (class "Default")
      (node (ref "IC1") (pin "35") (pinfunction "SCL_35") (pintype "open_collector"))
    )
    (net (code "77") (name "unconnected-(IC1-SDA-Pad34)") (class "Default")
      (node (ref "IC1") (pin "34") (pinfunction "SDA_34") (pintype "open_collector"))
    )
    (net (code "78") (name "unconnected-(IC3-TAB-Pad4)") (class "Default")
      (node (ref "IC3") (pin "4") (pinfunction "TAB_4") (pintype "bidirectional"))
    )
    (net (code "79") (name "unconnected-(IC4A-O-Pad12)") (class "Default")
      (node (ref "IC4") (pin "12") (pinfunction "O_12") (pintype "output"))
    )
    (net (code "80") (name "unconnected-(IC4B-O-Pad10)") (class "Default")
      (node (ref "IC4") (pin "10") (pinfunction "O_10") (pintype "output"))
    )
  )
)
